# RF_INPUT_DIFF.net
KiCad netlist of a schematic drawn in EAGLE
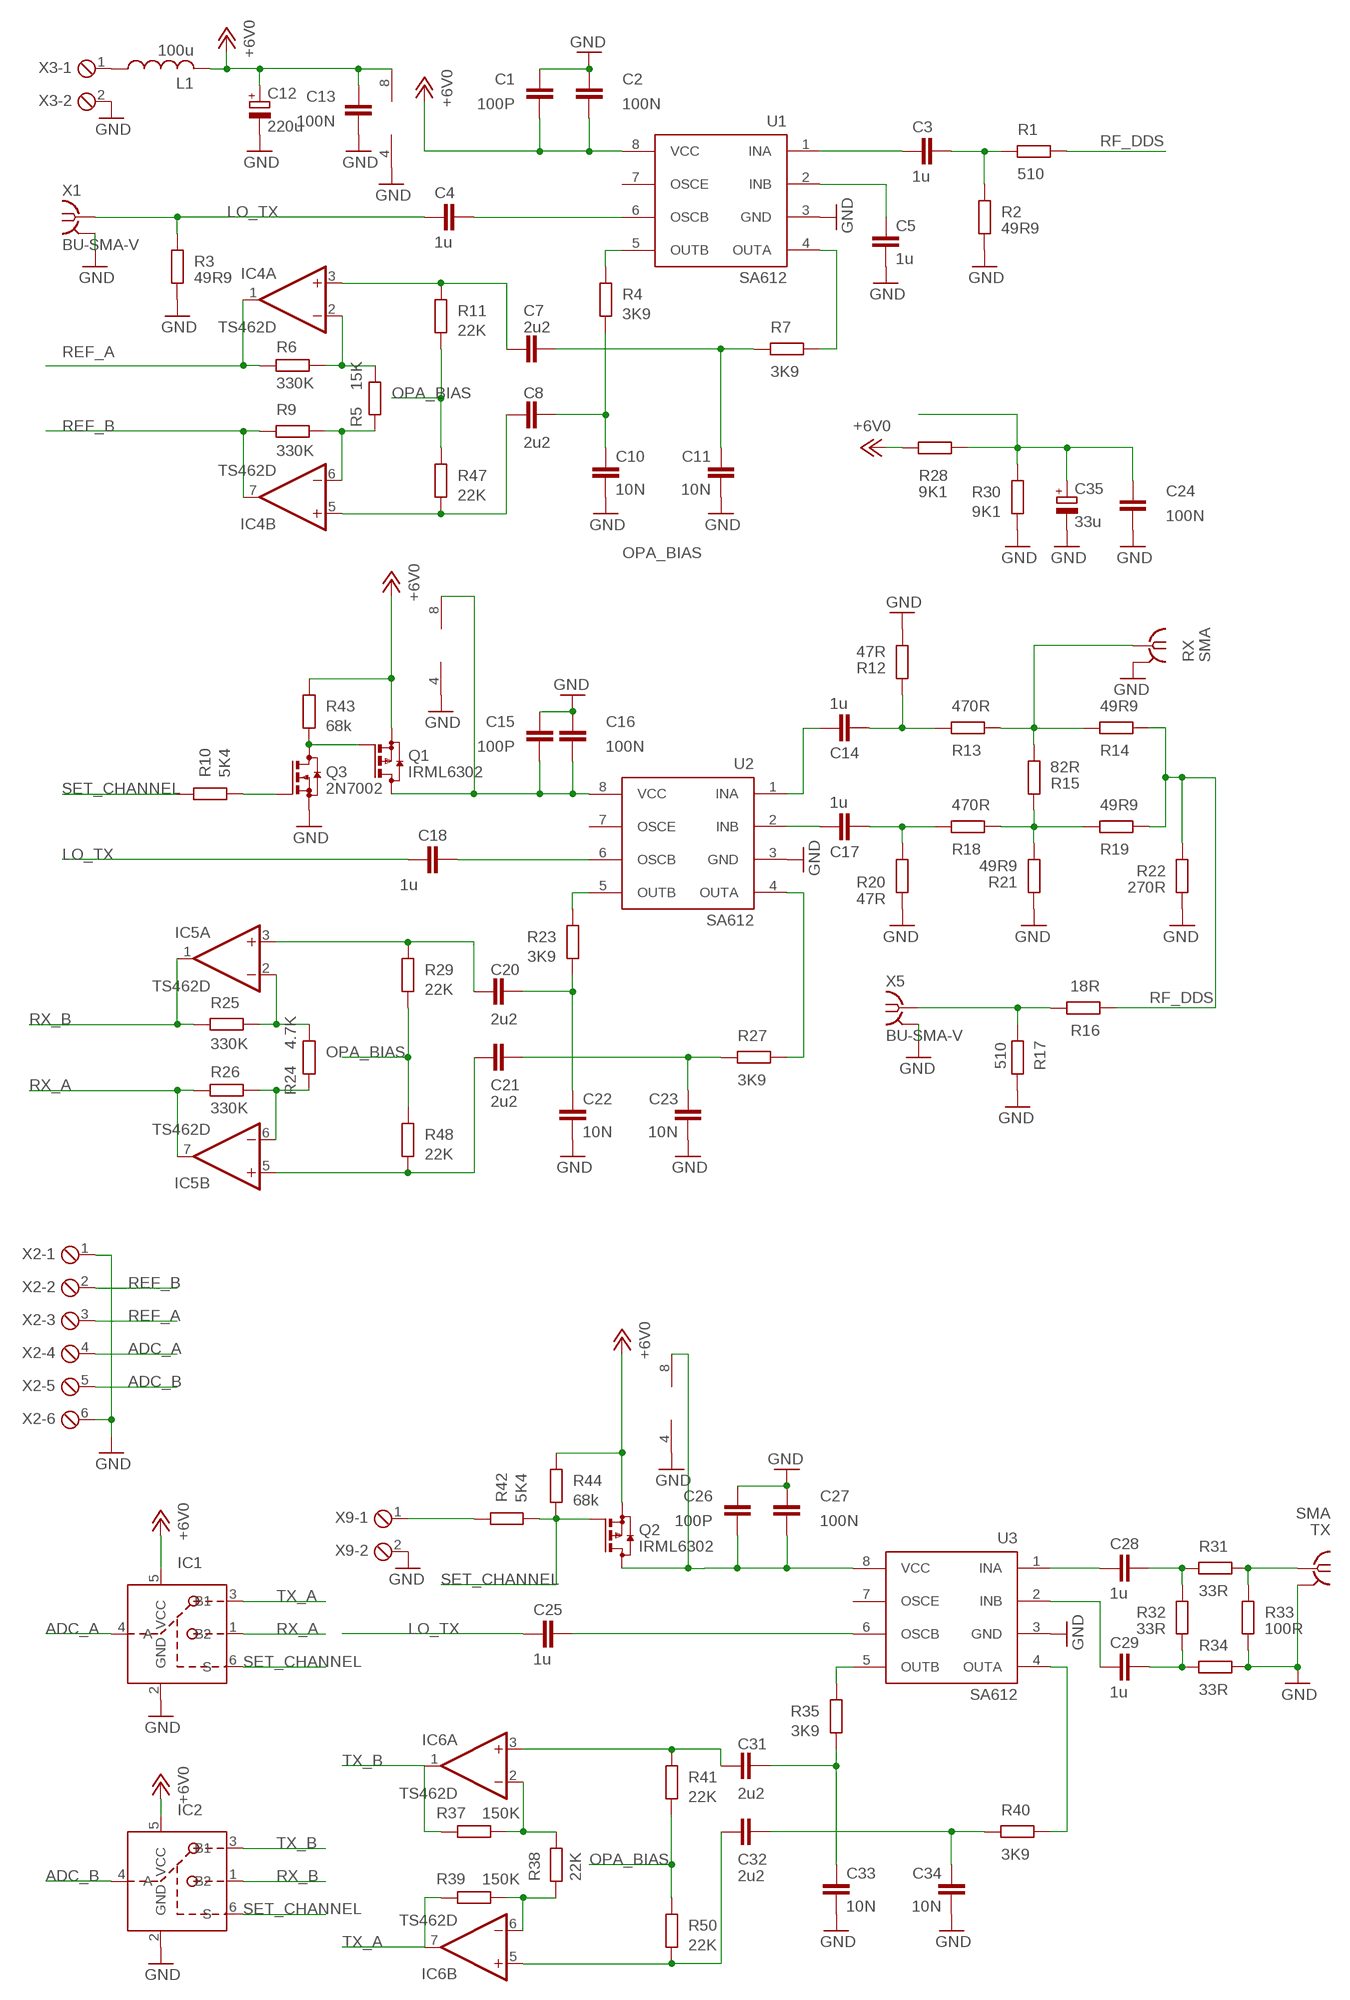
[diagram p0: schematic, sheet 1]

(export (version "E")
  (design (tool "Eeschema 10.0.6"))
  (components
    (comp (ref "C1")
      (value "100P")
      (footprint "eagle-import:C0805")
      (libsource (lib "eagle-import") (part "C-EUC0805"))
    )
    (comp (ref "C2")
      (value "100N")
      (footprint "eagle-import:C0603")
      (libsource (lib "eagle-import") (part "C-EUC0603"))
    )
    (comp (ref "C3")
      (value "1u")
      (footprint "eagle-import:C0603")
      (libsource (lib "eagle-import") (part "C-EUC0603"))
    )
    (comp (ref "C4")
      (value "1u")
      (footprint "eagle-import:C0805")
      (libsource (lib "eagle-import") (part "C-EUC0805"))
    )
    (comp (ref "C5")
      (value "1u")
      (footprint "eagle-import:C0603")
      (libsource (lib "eagle-import") (part "C-EUC0603"))
    )
    (comp (ref "C7")
      (value "2u2")
      (footprint "eagle-import:C0805")
      (libsource (lib "eagle-import") (part "C-EUC0805"))
    )
    (comp (ref "C8")
      (value "2u2")
      (footprint "eagle-import:C0805")
      (libsource (lib "eagle-import") (part "C-EUC0805"))
    )
    (comp (ref "C10")
      (value "10N")
      (footprint "eagle-import:C0805")
      (libsource (lib "eagle-import") (part "C-EUC0805"))
    )
    (comp (ref "C11")
      (value "10N")
      (footprint "eagle-import:C0805")
      (libsource (lib "eagle-import") (part "C-EUC0805"))
    )
    (comp (ref "C12")
      (value "220u")
      (footprint "eagle-import:153CLV-0605")
      (libsource (lib "eagle-import") (part "CPOL-EU153CLV-0605"))
    )
    (comp (ref "C13")
      (value "100N")
      (footprint "eagle-import:C0603")
      (libsource (lib "eagle-import") (part "C-EUC0603"))
    )
    (comp (ref "C14")
      (value "1u")
      (footprint "eagle-import:C0603")
      (libsource (lib "eagle-import") (part "C-EUC0603"))
    )
    (comp (ref "C15")
      (value "100P")
      (footprint "eagle-import:C0805")
      (libsource (lib "eagle-import") (part "C-EUC0805"))
    )
    (comp (ref "C16")
      (value "100N")
      (footprint "eagle-import:C0603")
      (libsource (lib "eagle-import") (part "C-EUC0603"))
    )
    (comp (ref "C17")
      (value "1u")
      (footprint "eagle-import:C0603")
      (libsource (lib "eagle-import") (part "C-EUC0603"))
    )
    (comp (ref "C18")
      (value "1u")
      (footprint "eagle-import:C0805")
      (libsource (lib "eagle-import") (part "C-EUC0805"))
    )
    (comp (ref "C20")
      (value "2u2")
      (footprint "eagle-import:C0805")
      (libsource (lib "eagle-import") (part "C-EUC0805"))
    )
    (comp (ref "C21")
      (value "2u2")
      (footprint "eagle-import:C0805")
      (libsource (lib "eagle-import") (part "C-EUC0805"))
    )
    (comp (ref "C22")
      (value "10N")
      (footprint "eagle-import:C0805")
      (libsource (lib "eagle-import") (part "C-EUC0805"))
    )
    (comp (ref "C23")
      (value "10N")
      (footprint "eagle-import:C0805")
      (libsource (lib "eagle-import") (part "C-EUC0805"))
    )
    (comp (ref "C24")
      (value "100N")
      (footprint "eagle-import:C0603")
      (libsource (lib "eagle-import") (part "C-EUC0603"))
    )
    (comp (ref "C25")
      (value "1u")
      (footprint "eagle-import:C0805")
      (libsource (lib "eagle-import") (part "C-EUC0805"))
    )
    (comp (ref "C26")
      (value "100P")
      (footprint "eagle-import:C0805")
      (libsource (lib "eagle-import") (part "C-EUC0805"))
    )
    (comp (ref "C27")
      (value "100N")
      (footprint "eagle-import:C0603")
      (libsource (lib "eagle-import") (part "C-EUC0603"))
    )
    (comp (ref "C28")
      (value "1u")
      (footprint "eagle-import:C0603")
      (libsource (lib "eagle-import") (part "C-EUC0603"))
    )
    (comp (ref "C29")
      (value "1u")
      (footprint "eagle-import:C0603")
      (libsource (lib "eagle-import") (part "C-EUC0603"))
    )
    (comp (ref "C31")
      (value "2u2")
      (footprint "eagle-import:C0805")
      (libsource (lib "eagle-import") (part "C-EUC0805"))
    )
    (comp (ref "C32")
      (value "2u2")
      (footprint "eagle-import:C0805")
      (libsource (lib "eagle-import") (part "C-EUC0805"))
    )
    (comp (ref "C33")
      (value "10N")
      (footprint "eagle-import:C0805")
      (libsource (lib "eagle-import") (part "C-EUC0805"))
    )
    (comp (ref "C34")
      (value "10N")
      (footprint "eagle-import:C0805")
      (libsource (lib "eagle-import") (part "C-EUC0805"))
    )
    (comp (ref "C35")
      (value "33u")
      (footprint "eagle-import:153CLV-0605")
      (libsource (lib "eagle-import") (part "CPOL-EU153CLV-0605"))
    )
    (comp (ref "IC1")
      (value "SN74LVC1G3157DBVR")
      (footprint "eagle-import:SOT23-6")
      (libsource (lib "eagle-import") (part "SN74LVC1G3157DBVR"))
    )
    (comp (ref "IC2")
      (value "SN74LVC1G3157DBVR")
      (footprint "eagle-import:SOT23-6")
      (libsource (lib "eagle-import") (part "SN74LVC1G3157DBVR"))
    )
    (comp (ref "IC4")
      (value "TS462D")
      (footprint "eagle-import:SO08")
      (libsource (lib "eagle-import") (part "LM358D"))
    )
    (comp (ref "IC5")
      (value "TS462D")
      (footprint "eagle-import:SO08")
      (libsource (lib "eagle-import") (part "LM358D"))
    )
    (comp (ref "IC6")
      (value "TS462D")
      (footprint "eagle-import:SO08")
      (libsource (lib "eagle-import") (part "LM358D"))
    )
    (comp (ref "L1")
      (value "100u")
      (footprint "eagle-import:0207_12")
      (libsource (lib "eagle-import") (part "L-US0207/12"))
    )
    (comp (ref "Q1")
      (value "IRML6302")
      (footprint "eagle-import:SOT23")
      (libsource (lib "eagle-import") (part "BSS84"))
    )
    (comp (ref "Q2")
      (value "IRML6302")
      (footprint "eagle-import:SOT23")
      (libsource (lib "eagle-import") (part "BSS84"))
    )
    (comp (ref "Q3")
      (value "2N7002")
      (footprint "eagle-import:SOT23")
      (libsource (lib "eagle-import") (part "BSS123"))
    )
    (comp (ref "R1")
      (value "510")
      (footprint "eagle-import:R0603")
      (libsource (lib "eagle-import") (part "R-EU_R0603"))
    )
    (comp (ref "R2")
      (value "49R9")
      (footprint "eagle-import:R0805")
      (libsource (lib "eagle-import") (part "R-EU_R0805"))
    )
    (comp (ref "R3")
      (value "49R9")
      (footprint "eagle-import:R0805")
      (libsource (lib "eagle-import") (part "R-EU_R0805"))
    )
    (comp (ref "R4")
      (value "3K9")
      (footprint "eagle-import:R0603")
      (libsource (lib "eagle-import") (part "R-EU_R0603"))
    )
    (comp (ref "R5")
      (value "15K")
      (footprint "eagle-import:R0603")
      (libsource (lib "eagle-import") (part "R-EU_R0603"))
    )
    (comp (ref "R6")
      (value "330K")
      (footprint "eagle-import:R0603")
      (libsource (lib "eagle-import") (part "R-EU_R0603"))
    )
    (comp (ref "R7")
      (value "3K9")
      (footprint "eagle-import:R0603")
      (libsource (lib "eagle-import") (part "R-EU_R0603"))
    )
    (comp (ref "R9")
      (value "330K")
      (footprint "eagle-import:R0603")
      (libsource (lib "eagle-import") (part "R-EU_R0603"))
    )
    (comp (ref "R10")
      (value "5K4")
      (footprint "eagle-import:R0603")
      (libsource (lib "eagle-import") (part "R-EU_R0603"))
    )
    (comp (ref "R11")
      (value "22K")
      (footprint "eagle-import:R0603")
      (libsource (lib "eagle-import") (part "R-EU_R0603"))
    )
    (comp (ref "R12")
      (value "47R")
      (footprint "eagle-import:R0603")
      (libsource (lib "eagle-import") (part "R-EU_R0603"))
    )
    (comp (ref "R13")
      (value "470R")
      (footprint "eagle-import:R0603")
      (libsource (lib "eagle-import") (part "R-EU_R0603"))
    )
    (comp (ref "R14")
      (value "49R9")
      (footprint "eagle-import:R0805")
      (libsource (lib "eagle-import") (part "R-EU_R0805"))
    )
    (comp (ref "R15")
      (value "82R")
      (footprint "eagle-import:R0603")
      (libsource (lib "eagle-import") (part "R-EU_R0603"))
    )
    (comp (ref "R16")
      (value "18R")
      (footprint "eagle-import:R0603")
      (libsource (lib "eagle-import") (part "R-EU_R0603"))
    )
    (comp (ref "R17")
      (value "510")
      (footprint "eagle-import:R0603")
      (libsource (lib "eagle-import") (part "R-EU_R0603"))
    )
    (comp (ref "R18")
      (value "470R")
      (footprint "eagle-import:R0603")
      (libsource (lib "eagle-import") (part "R-EU_R0603"))
    )
    (comp (ref "R19")
      (value "49R9")
      (footprint "eagle-import:R0805")
      (libsource (lib "eagle-import") (part "R-EU_R0805"))
    )
    (comp (ref "R20")
      (value "47R")
      (footprint "eagle-import:R0603")
      (libsource (lib "eagle-import") (part "R-EU_R0603"))
    )
    (comp (ref "R21")
      (value "49R9")
      (footprint "eagle-import:R0805")
      (libsource (lib "eagle-import") (part "R-EU_R0805"))
    )
    (comp (ref "R22")
      (value "270R")
      (footprint "eagle-import:R0603")
      (libsource (lib "eagle-import") (part "R-EU_R0603"))
    )
    (comp (ref "R23")
      (value "3K9")
      (footprint "eagle-import:R0603")
      (libsource (lib "eagle-import") (part "R-EU_R0603"))
    )
    (comp (ref "R24")
      (value "4.7K")
      (footprint "eagle-import:R0603")
      (libsource (lib "eagle-import") (part "R-EU_R0603"))
    )
    (comp (ref "R25")
      (value "330K")
      (footprint "eagle-import:R0603")
      (libsource (lib "eagle-import") (part "R-EU_R0603"))
    )
    (comp (ref "R26")
      (value "330K")
      (footprint "eagle-import:R0603")
      (libsource (lib "eagle-import") (part "R-EU_R0603"))
    )
    (comp (ref "R27")
      (value "3K9")
      (footprint "eagle-import:R0603")
      (libsource (lib "eagle-import") (part "R-EU_R0603"))
    )
    (comp (ref "R28")
      (value "9K1")
      (footprint "eagle-import:R0603")
      (libsource (lib "eagle-import") (part "R-EU_R0603"))
    )
    (comp (ref "R29")
      (value "22K")
      (footprint "eagle-import:R0603")
      (libsource (lib "eagle-import") (part "R-EU_R0603"))
    )
    (comp (ref "R30")
      (value "9K1")
      (footprint "eagle-import:R0603")
      (libsource (lib "eagle-import") (part "R-EU_R0603"))
    )
    (comp (ref "R31")
      (value "33R")
      (footprint "eagle-import:R0603")
      (libsource (lib "eagle-import") (part "R-EU_R0603"))
    )
    (comp (ref "R32")
      (value "33R")
      (footprint "eagle-import:R0603")
      (libsource (lib "eagle-import") (part "R-EU_R0603"))
    )
    (comp (ref "R33")
      (value "100R")
      (footprint "eagle-import:R0603")
      (libsource (lib "eagle-import") (part "R-EU_R0603"))
    )
    (comp (ref "R34")
      (value "33R")
      (footprint "eagle-import:R0603")
      (libsource (lib "eagle-import") (part "R-EU_R0603"))
    )
    (comp (ref "R35")
      (value "3K9")
      (footprint "eagle-import:R0603")
      (libsource (lib "eagle-import") (part "R-EU_R0603"))
    )
    (comp (ref "R37")
      (value "150K")
      (footprint "eagle-import:R0603")
      (libsource (lib "eagle-import") (part "R-EU_R0603"))
    )
    (comp (ref "R38")
      (value "22K")
      (footprint "eagle-import:R0603")
      (libsource (lib "eagle-import") (part "R-EU_R0603"))
    )
    (comp (ref "R39")
      (value "150K")
      (footprint "eagle-import:R0603")
      (libsource (lib "eagle-import") (part "R-EU_R0603"))
    )
    (comp (ref "R40")
      (value "3K9")
      (footprint "eagle-import:R0603")
      (libsource (lib "eagle-import") (part "R-EU_R0603"))
    )
    (comp (ref "R41")
      (value "22K")
      (footprint "eagle-import:R0603")
      (libsource (lib "eagle-import") (part "R-EU_R0603"))
    )
    (comp (ref "R42")
      (value "5K4")
      (footprint "eagle-import:R0603")
      (libsource (lib "eagle-import") (part "R-EU_R0603"))
    )
    (comp (ref "R43")
      (value "68k")
      (footprint "eagle-import:R0603")
      (libsource (lib "eagle-import") (part "R-EU_R0603"))
    )
    (comp (ref "R44")
      (value "68k")
      (footprint "eagle-import:R0603")
      (libsource (lib "eagle-import") (part "R-EU_R0603"))
    )
    (comp (ref "R47")
      (value "22K")
      (footprint "eagle-import:R0603")
      (libsource (lib "eagle-import") (part "R-EU_R0603"))
    )
    (comp (ref "R48")
      (value "22K")
      (footprint "eagle-import:R0603")
      (libsource (lib "eagle-import") (part "R-EU_R0603"))
    )
    (comp (ref "R50")
      (value "22K")
      (footprint "eagle-import:R0603")
      (libsource (lib "eagle-import") (part "R-EU_R0603"))
    )
    (comp (ref "RX")
      (value "SMA")
      (footprint "eagle-import:J502-ND-142-0701-801_806")
      (fields (field (name "MF") "JOHNSON COMPONENTS") (field (name "MPN") "142-0701-801"))
      (libsource (lib "eagle-import") (part "SMA-142-0701-801/806"))
    )
    (comp (ref "TX")
      (value "SMA")
      (footprint "eagle-import:J502-ND-142-0701-801_806")
      (fields (field (name "MF") "JOHNSON COMPONENTS") (field (name "MPN") "142-0701-801"))
      (libsource (lib "eagle-import") (part "SMA-142-0701-801/806"))
    )
    (comp (ref "U1")
      (value "SA612")
      (footprint "eagle-import:SO8")
      (libsource (lib "eagle-import") (part "SA612"))
    )
    (comp (ref "U2")
      (value "SA612")
      (footprint "eagle-import:SO8")
      (libsource (lib "eagle-import") (part "SA612"))
    )
    (comp (ref "U3")
      (value "SA612")
      (footprint "eagle-import:SO8")
      (libsource (lib "eagle-import") (part "SA612"))
    )
    (comp (ref "X1")
      (value "BU-SMA-V")
      (footprint "eagle-import:BU-SMA-V")
      (libsource (lib "eagle-import") (part "BU-SMA-V"))
    )
    (comp (ref "X2")
      (value "MPT6")
      (footprint "eagle-import:6POL254")
      (libsource (lib "eagle-import") (part "MPT6"))
    )
    (comp (ref "X3")
      (value "MPT2")
      (footprint "eagle-import:2POL254")
      (libsource (lib "eagle-import") (part "MPT2"))
    )
    (comp (ref "X5")
      (value "BU-SMA-V")
      (footprint "eagle-import:BU-SMA-V")
      (libsource (lib "eagle-import") (part "BU-SMA-V"))
    )
    (comp (ref "X9")
      (value "MPT2")
      (footprint "eagle-import:2POL254")
      (libsource (lib "eagle-import") (part "MPT2"))
    )
  )
  (nets
    (net (code "1") (name "+6V0") (class "Default")
      (node (ref "C1") (pin "1") (pinfunction "1_1") (pintype "passive"))
      (node (ref "C12") (pin "+") (pinfunction "+_+") (pintype "passive"))
      (node (ref "C13") (pin "1") (pinfunction "1_1") (pintype "passive"))
      (node (ref "C2") (pin "1") (pinfunction "1_1") (pintype "passive"))
      (node (ref "IC1") (pin "5") (pinfunction "VCC_5") (pintype "power_in"))
      (node (ref "IC2") (pin "5") (pinfunction "VCC_5") (pintype "power_in"))
      (node (ref "IC4") (pin "8") (pinfunction "V+_8") (pintype "power_in"))
      (node (ref "L1") (pin "2") (pinfunction "2_2") (pintype "passive"))
      (node (ref "Q1") (pin "2") (pinfunction "S_2") (pintype "passive"))
      (node (ref "Q2") (pin "2") (pinfunction "S_2") (pintype "passive"))
      (node (ref "R28") (pin "2") (pinfunction "2_2") (pintype "passive"))
      (node (ref "R43") (pin "1") (pinfunction "1_1") (pintype "passive"))
      (node (ref "R44") (pin "1") (pinfunction "1_1") (pintype "passive"))
      (node (ref "U1") (pin "8") (pinfunction "VCC_8") (pintype "bidirectional"))
    )
    (net (code "2") (name "/ADC_A") (class "Default")
      (node (ref "IC1") (pin "4") (pinfunction "A_4") (pintype "bidirectional"))
      (node (ref "X2") (pin "4") (pinfunction "1_4") (pintype "passive"))
    )
    (net (code "3") (name "/ADC_B") (class "Default")
      (node (ref "IC2") (pin "4") (pinfunction "A_4") (pintype "bidirectional"))
      (node (ref "X2") (pin "5") (pinfunction "1_5") (pintype "passive"))
    )
    (net (code "4") (name "/LO_TX") (class "Default")
      (node (ref "C18") (pin "1") (pinfunction "1_1") (pintype "passive"))
      (node (ref "C25") (pin "1") (pinfunction "1_1") (pintype "passive"))
      (node (ref "C4") (pin "1") (pinfunction "1_1") (pintype "passive"))
      (node (ref "R3") (pin "1") (pinfunction "1_1") (pintype "passive"))
      (node (ref "X1") (pin "1") (pinfunction "1_1") (pintype "passive"))
    )
    (net (code "5") (name "/OPA_BIAS") (class "Default")
      (node (ref "C24") (pin "2") (pinfunction "2_2") (pintype "passive"))
      (node (ref "C35") (pin "+") (pinfunction "+_+") (pintype "passive"))
      (node (ref "R11") (pin "2") (pinfunction "2_2") (pintype "passive"))
      (node (ref "R28") (pin "1") (pinfunction "1_1") (pintype "passive"))
      (node (ref "R29") (pin "2") (pinfunction "2_2") (pintype "passive"))
      (node (ref "R30") (pin "1") (pinfunction "1_1") (pintype "passive"))
      (node (ref "R41") (pin "2") (pinfunction "2_2") (pintype "passive"))
      (node (ref "R47") (pin "1") (pinfunction "1_1") (pintype "passive"))
      (node (ref "R48") (pin "1") (pinfunction "1_1") (pintype "passive"))
      (node (ref "R50") (pin "1") (pinfunction "1_1") (pintype "passive"))
    )
    (net (code "6") (name "/REF_A") (class "Default")
      (node (ref "IC4") (pin "1") (pinfunction "OUT_1") (pintype "output"))
      (node (ref "R6") (pin "2") (pinfunction "2_2") (pintype "passive"))
      (node (ref "X2") (pin "3") (pinfunction "1_3") (pintype "passive"))
    )
    (net (code "7") (name "/REF_B") (class "Default")
      (node (ref "IC4") (pin "7") (pinfunction "OUT_7") (pintype "output"))
      (node (ref "R9") (pin "2") (pinfunction "2_2") (pintype "passive"))
      (node (ref "X2") (pin "2") (pinfunction "1_2") (pintype "passive"))
    )
    (net (code "8") (name "/RF_DDS") (class "Default")
      (node (ref "R1") (pin "1") (pinfunction "1_1") (pintype "passive"))
      (node (ref "R16") (pin "1") (pinfunction "1_1") (pintype "passive"))
      (node (ref "R17") (pin "1") (pinfunction "1_1") (pintype "passive"))
      (node (ref "X5") (pin "1") (pinfunction "1_1") (pintype "passive"))
    )
    (net (code "9") (name "/RX_A") (class "Default")
      (node (ref "IC1") (pin "1") (pinfunction "B2_1") (pintype "bidirectional"))
      (node (ref "IC5") (pin "7") (pinfunction "OUT_7") (pintype "output"))
      (node (ref "R26") (pin "2") (pinfunction "2_2") (pintype "passive"))
    )
    (net (code "10") (name "/RX_B") (class "Default")
      (node (ref "IC2") (pin "1") (pinfunction "B2_1") (pintype "bidirectional"))
      (node (ref "IC5") (pin "1") (pinfunction "OUT_1") (pintype "output"))
      (node (ref "R25") (pin "2") (pinfunction "2_2") (pintype "passive"))
    )
    (net (code "11") (name "/SET_CHANNEL") (class "Default")
      (node (ref "IC1") (pin "6") (pinfunction "S_6") (pintype "bidirectional"))
      (node (ref "IC2") (pin "6") (pinfunction "S_6") (pintype "bidirectional"))
      (node (ref "Q2") (pin "1") (pinfunction "G_1") (pintype "passive"))
      (node (ref "R10") (pin "1") (pinfunction "1_1") (pintype "passive"))
      (node (ref "R42") (pin "2") (pinfunction "2_2") (pintype "passive"))
      (node (ref "R44") (pin "2") (pinfunction "2_2") (pintype "passive"))
    )
    (net (code "12") (name "/TX_A") (class "Default")
      (node (ref "IC1") (pin "3") (pinfunction "B1_3") (pintype "bidirectional"))
      (node (ref "IC6") (pin "7") (pinfunction "OUT_7") (pintype "output"))
      (node (ref "R39") (pin "2") (pinfunction "2_2") (pintype "passive"))
    )
    (net (code "13") (name "/TX_B") (class "Default")
      (node (ref "IC2") (pin "3") (pinfunction "B1_3") (pintype "bidirectional"))
      (node (ref "IC6") (pin "1") (pinfunction "OUT_1") (pintype "output"))
      (node (ref "R37") (pin "2") (pinfunction "2_2") (pintype "passive"))
    )
    (net (code "14") (name "GND") (class "Default")
      (node (ref "C1") (pin "2") (pinfunction "2_2") (pintype "passive"))
      (node (ref "C10") (pin "2") (pinfunction "2_2") (pintype "passive"))
      (node (ref "C11") (pin "2") (pinfunction "2_2") (pintype "passive"))
      (node (ref "C12") (pin "-") (pinfunction "-_-") (pintype "passive"))
      (node (ref "C13") (pin "2") (pinfunction "2_2") (pintype "passive"))
      (node (ref "C15") (pin "2") (pinfunction "2_2") (pintype "passive"))
      (node (ref "C16") (pin "2") (pinfunction "2_2") (pintype "passive"))
      (node (ref "C2") (pin "2") (pinfunction "2_2") (pintype "passive"))
      (node (ref "C22") (pin "2") (pinfunction "2_2") (pintype "passive"))
      (node (ref "C23") (pin "2") (pinfunction "2_2") (pintype "passive"))
      (node (ref "C24") (pin "1") (pinfunction "1_1") (pintype "passive"))
      (node (ref "C26") (pin "2") (pinfunction "2_2") (pintype "passive"))
      (node (ref "C27") (pin "2") (pinfunction "2_2") (pintype "passive"))
      (node (ref "C33") (pin "2") (pinfunction "2_2") (pintype "passive"))
      (node (ref "C34") (pin "2") (pinfunction "2_2") (pintype "passive"))
      (node (ref "C35") (pin "-") (pinfunction "-_-") (pintype "passive"))
      (node (ref "C5") (pin "2") (pinfunction "2_2") (pintype "passive"))
      (node (ref "IC1") (pin "2") (pinfunction "GND_2") (pintype "power_in"))
      (node (ref "IC2") (pin "2") (pinfunction "GND_2") (pintype "power_in"))
      (node (ref "IC4") (pin "4") (pinfunction "V-_4") (pintype "power_in"))
      (node (ref "IC5") (pin "4") (pinfunction "V-_4") (pintype "power_in"))
      (node (ref "IC6") (pin "4") (pinfunction "V-_4") (pintype "power_in"))
      (node (ref "Q3") (pin "2") (pinfunction "S_2") (pintype "passive"))
      (node (ref "R12") (pin "2") (pinfunction "2_2") (pintype "passive"))
      (node (ref "R17") (pin "2") (pinfunction "2_2") (pintype "passive"))
      (node (ref "R2") (pin "1") (pinfunction "1_1") (pintype "passive"))
      (node (ref "R20") (pin "1") (pinfunction "1_1") (pintype "passive"))
      (node (ref "R21") (pin "1") (pinfunction "1_1") (pintype "passive"))
      (node (ref "R22") (pin "2") (pinfunction "2_2") (pintype "passive"))
      (node (ref "R3") (pin "2") (pinfunction "2_2") (pintype "passive"))
      (node (ref "R30") (pin "2") (pinfunction "2_2") (pintype "passive"))
      (node (ref "R33") (pin "2") (pinfunction "2_2") (pintype "passive"))
      (node (ref "R34") (pin "1") (pinfunction "1_1") (pintype "passive"))
      (node (ref "RX") (pin "G@1") (pinfunction "2_G@1") (pintype "passive"))
      (node (ref "RX") (pin "G@2") (pinfunction "2_G@2") (pintype "passive"))
      (node (ref "RX") (pin "G@3") (pinfunction "2_G@3") (pintype "passive"))
      (node (ref "RX") (pin "G@4") (pinfunction "2_G@4") (pintype "passive"))
      (node (ref "TX") (pin "G@1") (pinfunction "2_G@1") (pintype "passive"))
      (node (ref "TX") (pin "G@2") (pinfunction "2_G@2") (pintype "passive"))
      (node (ref "TX") (pin "G@3") (pinfunction "2_G@3") (pintype "passive"))
      (node (ref "TX") (pin "G@4") (pinfunction "2_G@4") (pintype "passive"))
      (node (ref "U1") (pin "3") (pinfunction "GND_3") (pintype "bidirectional"))
      (node (ref "U2") (pin "3") (pinfunction "GND_3") (pintype "bidirectional"))
      (node (ref "U3") (pin "3") (pinfunction "GND_3") (pintype "bidirectional"))
      (node (ref "X1") (pin "2") (pinfunction "2_2") (pintype "passive"))
      (node (ref "X1") (pin "3") (pinfunction "2_3") (pintype "passive"))
      (node (ref "X1") (pin "4") (pinfunction "2_4") (pintype "passive"))
      (node (ref "X1") (pin "5") (pinfunction "2_5") (pintype "passive"))
      (node (ref "X2") (pin "1") (pinfunction "1_1") (pintype "passive"))
      (node (ref "X2") (pin "6") (pinfunction "1_6") (pintype "passive"))
      (node (ref "X3") (pin "2") (pinfunction "1_2") (pintype "passive"))
      (node (ref "X5") (pin "2") (pinfunction "2_2") (pintype "passive"))
      (node (ref "X5") (pin "3") (pinfunction "2_3") (pintype "passive"))
      (node (ref "X5") (pin "4") (pinfunction "2_4") (pintype "passive"))
      (node (ref "X5") (pin "5") (pinfunction "2_5") (pintype "passive"))
      (node (ref "X9") (pin "2") (pinfunction "1_2") (pintype "passive"))
    )
    (net (code "15") (name "Net-(C3-Pad2)") (class "Default")
      (node (ref "C3") (pin "2") (pinfunction "2_2") (pintype "passive"))
      (node (ref "R1") (pin "2") (pinfunction "2_2") (pintype "passive"))
      (node (ref "R2") (pin "2") (pinfunction "2_2") (pintype "passive"))
    )
    (net (code "16") (name "Net-(C10-Pad1)") (class "Default")
      (node (ref "C10") (pin "1") (pinfunction "1_1") (pintype "passive"))
      (node (ref "C8") (pin "2") (pinfunction "2_2") (pintype "passive"))
      (node (ref "R4") (pin "2") (pinfunction "2_2") (pintype "passive"))
    )
    (net (code "17") (name "Net-(C11-Pad1)") (class "Default")
      (node (ref "C11") (pin "1") (pinfunction "1_1") (pintype "passive"))
      (node (ref "C7") (pin "2") (pinfunction "2_2") (pintype "passive"))
      (node (ref "R7") (pin "2") (pinfunction "2_2") (pintype "passive"))
    )
    (net (code "18") (name "Net-(C14-Pad2)") (class "Default")
      (node (ref "C14") (pin "2") (pinfunction "2_2") (pintype "passive"))
      (node (ref "R12") (pin "1") (pinfunction "1_1") (pintype "passive"))
      (node (ref "R13") (pin "2") (pinfunction "2_2") (pintype "passive"))
    )
    (net (code "19") (name "Net-(C17-Pad2)") (class "Default")
      (node (ref "C17") (pin "2") (pinfunction "2_2") (pintype "passive"))
      (node (ref "R18") (pin "2") (pinfunction "2_2") (pintype "passive"))
      (node (ref "R20") (pin "2") (pinfunction "2_2") (pintype "passive"))
    )
    (net (code "20") (name "Net-(C20-Pad2)") (class "Default")
      (node (ref "C20") (pin "2") (pinfunction "2_2") (pintype "passive"))
      (node (ref "C22") (pin "1") (pinfunction "1_1") (pintype "passive"))
      (node (ref "R23") (pin "2") (pinfunction "2_2") (pintype "passive"))
    )
    (net (code "21") (name "Net-(C21-Pad2)") (class "Default")
      (node (ref "C21") (pin "2") (pinfunction "2_2") (pintype "passive"))
      (node (ref "C23") (pin "1") (pinfunction "1_1") (pintype "passive"))
      (node (ref "R27") (pin "2") (pinfunction "2_2") (pintype "passive"))
    )
    (net (code "22") (name "Net-(C28-Pad2)") (class "Default")
      (node (ref "C28") (pin "2") (pinfunction "2_2") (pintype "passive"))
      (node (ref "R31") (pin "2") (pinfunction "2_2") (pintype "passive"))
      (node (ref "R32") (pin "1") (pinfunction "1_1") (pintype "passive"))
    )
    (net (code "23") (name "Net-(C29-Pad2)") (class "Default")
      (node (ref "C29") (pin "2") (pinfunction "2_2") (pintype "passive"))
      (node (ref "R32") (pin "2") (pinfunction "2_2") (pintype "passive"))
      (node (ref "R34") (pin "2") (pinfunction "2_2") (pintype "passive"))
    )
    (net (code "24") (name "Net-(C31-Pad2)") (class "Default")
      (node (ref "C31") (pin "2") (pinfunction "2_2") (pintype "passive"))
      (node (ref "C33") (pin "1") (pinfunction "1_1") (pintype "passive"))
      (node (ref "R35") (pin "2") (pinfunction "2_2") (pintype "passive"))
    )
    (net (code "25") (name "Net-(C32-Pad2)") (class "Default")
      (node (ref "C32") (pin "2") (pinfunction "2_2") (pintype "passive"))
      (node (ref "C34") (pin "1") (pinfunction "1_1") (pintype "passive"))
      (node (ref "R40") (pin "2") (pinfunction "2_2") (pintype "passive"))
    )
    (net (code "26") (name "Net-(IC4A-+IN)") (class "Default")
      (node (ref "C7") (pin "1") (pinfunction "1_1") (pintype "passive"))
      (node (ref "IC4") (pin "3") (pinfunction "+IN_3") (pintype "input"))
      (node (ref "R11") (pin "1") (pinfunction "1_1") (pintype "passive"))
    )
    (net (code "27") (name "Net-(IC4A--IN)") (class "Default")
      (node (ref "IC4") (pin "2") (pinfunction "-IN_2") (pintype "input"))
      (node (ref "R5") (pin "1") (pinfunction "1_1") (pintype "passive"))
      (node (ref "R6") (pin "1") (pinfunction "1_1") (pintype "passive"))
    )
    (net (code "28") (name "Net-(IC4B-+IN)") (class "Default")
      (node (ref "C8") (pin "1") (pinfunction "1_1") (pintype "passive"))
      (node (ref "IC4") (pin "5") (pinfunction "+IN_5") (pintype "input"))
      (node (ref "R47") (pin "2") (pinfunction "2_2") (pintype "passive"))
    )
    (net (code "29") (name "Net-(IC4B--IN)") (class "Default")
      (node (ref "IC4") (pin "6") (pinfunction "-IN_6") (pintype "input"))
      (node (ref "R5") (pin "2") (pinfunction "2_2") (pintype "passive"))
      (node (ref "R9") (pin "1") (pinfunction "1_1") (pintype "passive"))
    )
    (net (code "30") (name "Net-(IC5A-+IN)") (class "Default")
      (node (ref "C20") (pin "1") (pinfunction "1_1") (pintype "passive"))
      (node (ref "IC5") (pin "3") (pinfunction "+IN_3") (pintype "input"))
      (node (ref "R29") (pin "1") (pinfunction "1_1") (pintype "passive"))
    )
    (net (code "31") (name "Net-(IC5A--IN)") (class "Default")
      (node (ref "IC5") (pin "2") (pinfunction "-IN_2") (pintype "input"))
      (node (ref "R24") (pin "1") (pinfunction "1_1") (pintype "passive"))
      (node (ref "R25") (pin "1") (pinfunction "1_1") (pintype "passive"))
    )
    (net (code "32") (name "Net-(IC5B-+IN)") (class "Default")
      (node (ref "C21") (pin "1") (pinfunction "1_1") (pintype "passive"))
      (node (ref "IC5") (pin "5") (pinfunction "+IN_5") (pintype "input"))
      (node (ref "R48") (pin "2") (pinfunction "2_2") (pintype "passive"))
    )
    (net (code "33") (name "Net-(IC5B--IN)") (class "Default")
      (node (ref "IC5") (pin "6") (pinfunction "-IN_6") (pintype "input"))
      (node (ref "R24") (pin "2") (pinfunction "2_2") (pintype "passive"))
      (node (ref "R26") (pin "1") (pinfunction "1_1") (pintype "passive"))
    )
    (net (code "34") (name "Net-(IC5C-V+)") (class "Default")
      (node (ref "C15") (pin "1") (pinfunction "1_1") (pintype "passive"))
      (node (ref "C16") (pin "1") (pinfunction "1_1") (pintype "passive"))
      (node (ref "IC5") (pin "8") (pinfunction "V+_8") (pintype "power_in"))
      (node (ref "Q1") (pin "3") (pinfunction "D_3") (pintype "passive"))
      (node (ref "U2") (pin "8") (pinfunction "VCC_8") (pintype "bidirectional"))
    )
    (net (code "35") (name "Net-(IC6A-+IN)") (class "Default")
      (node (ref "C31") (pin "1") (pinfunction "1_1") (pintype "passive"))
      (node (ref "IC6") (pin "3") (pinfunction "+IN_3") (pintype "input"))
      (node (ref "R41") (pin "1") (pinfunction "1_1") (pintype "passive"))
    )
    (net (code "36") (name "Net-(IC6A--IN)") (class "Default")
      (node (ref "IC6") (pin "2") (pinfunction "-IN_2") (pintype "input"))
      (node (ref "R37") (pin "1") (pinfunction "1_1") (pintype "passive"))
      (node (ref "R38") (pin "1") (pinfunction "1_1") (pintype "passive"))
    )
    (net (code "37") (name "Net-(IC6B-+IN)") (class "Default")
      (node (ref "C32") (pin "1") (pinfunction "1_1") (pintype "passive"))
      (node (ref "IC6") (pin "5") (pinfunction "+IN_5") (pintype "input"))
      (node (ref "R50") (pin "2") (pinfunction "2_2") (pintype "passive"))
    )
    (net (code "38") (name "Net-(IC6B--IN)") (class "Default")
      (node (ref "IC6") (pin "6") (pinfunction "-IN_6") (pintype "input"))
      (node (ref "R38") (pin "2") (pinfunction "2_2") (pintype "passive"))
      (node (ref "R39") (pin "1") (pinfunction "1_1") (pintype "passive"))
    )
    (net (code "39") (name "Net-(IC6C-V+)") (class "Default")
      (node (ref "C26") (pin "1") (pinfunction "1_1") (pintype "passive"))
      (node (ref "C27") (pin "1") (pinfunction "1_1") (pintype "passive"))
      (node (ref "IC6") (pin "8") (pinfunction "V+_8") (pintype "power_in"))
      (node (ref "Q2") (pin "3") (pinfunction "D_3") (pintype "passive"))
      (node (ref "U3") (pin "8") (pinfunction "VCC_8") (pintype "bidirectional"))
    )
    (net (code "40") (name "Net-(L1-Pad1)") (class "Default")
      (node (ref "L1") (pin "1") (pinfunction "1_1") (pintype "passive"))
      (node (ref "X3") (pin "1") (pinfunction "1_1") (pintype "passive"))
    )
    (net (code "41") (name "Net-(Q1-G)") (class "Default")
      (node (ref "Q1") (pin "1") (pinfunction "G_1") (pintype "passive"))
      (node (ref "Q3") (pin "3") (pinfunction "D_3") (pintype "passive"))
      (node (ref "R43") (pin "2") (pinfunction "2_2") (pintype "passive"))
    )
    (net (code "42") (name "Net-(Q3-G)") (class "Default")
      (node (ref "Q3") (pin "1") (pinfunction "G_1") (pintype "passive"))
      (node (ref "R10") (pin "2") (pinfunction "2_2") (pintype "passive"))
    )
    (net (code "43") (name "Net-(R13-Pad1)") (class "Default")
      (node (ref "R13") (pin "1") (pinfunction "1_1") (pintype "passive"))
      (node (ref "R14") (pin "2") (pinfunction "2_2") (pintype "passive"))
      (node (ref "R15") (pin "2") (pinfunction "2_2") (pintype "passive"))
      (node (ref "RX") (pin "1") (pinfunction "1_1") (pintype "passive"))
    )
    (net (code "44") (name "Net-(R14-Pad1)") (class "Default")
      (node (ref "R14") (pin "1") (pinfunction "1_1") (pintype "passive"))
      (node (ref "R16") (pin "2") (pinfunction "2_2") (pintype "passive"))
      (node (ref "R19") (pin "1") (pinfunction "1_1") (pintype "passive"))
      (node (ref "R22") (pin "1") (pinfunction "1_1") (pintype "passive"))
    )
    (net (code "45") (name "Net-(R15-Pad1)") (class "Default")
      (node (ref "R15") (pin "1") (pinfunction "1_1") (pintype "passive"))
      (node (ref "R18") (pin "1") (pinfunction "1_1") (pintype "passive"))
      (node (ref "R19") (pin "2") (pinfunction "2_2") (pintype "passive"))
      (node (ref "R21") (pin "2") (pinfunction "2_2") (pintype "passive"))
    )
    (net (code "46") (name "Net-(R31-Pad1)") (class "Default")
      (node (ref "R31") (pin "1") (pinfunction "1_1") (pintype "passive"))
      (node (ref "R33") (pin "1") (pinfunction "1_1") (pintype "passive"))
      (node (ref "TX") (pin "1") (pinfunction "1_1") (pintype "passive"))
    )
    (net (code "47") (name "Net-(R42-Pad1)") (class "Default")
      (node (ref "R42") (pin "1") (pinfunction "1_1") (pintype "passive"))
      (node (ref "X9") (pin "1") (pinfunction "1_1") (pintype "passive"))
    )
    (net (code "48") (name "Net-(U1-INA)") (class "Default")
      (node (ref "C3") (pin "1") (pinfunction "1_1") (pintype "passive"))
      (node (ref "U1") (pin "1") (pinfunction "INA_1") (pintype "bidirectional"))
    )
    (net (code "49") (name "Net-(U1-INB)") (class "Default")
      (node (ref "C5") (pin "1") (pinfunction "1_1") (pintype "passive"))
      (node (ref "U1") (pin "2") (pinfunction "INB_2") (pintype "bidirectional"))
    )
    (net (code "50") (name "Net-(U1-OSCB)") (class "Default")
      (node (ref "C4") (pin "2") (pinfunction "2_2") (pintype "passive"))
      (node (ref "U1") (pin "6") (pinfunction "OSCB_6") (pintype "bidirectional"))
    )
    (net (code "51") (name "Net-(U1-OUTA)") (class "Default")
      (node (ref "R7") (pin "1") (pinfunction "1_1") (pintype "passive"))
      (node (ref "U1") (pin "4") (pinfunction "OUTA_4") (pintype "bidirectional"))
    )
    (net (code "52") (name "Net-(U1-OUTB)") (class "Default")
      (node (ref "R4") (pin "1") (pinfunction "1_1") (pintype "passive"))
      (node (ref "U1") (pin "5") (pinfunction "OUTB_5") (pintype "bidirectional"))
    )
    (net (code "53") (name "Net-(U2-INA)") (class "Default")
      (node (ref "C14") (pin "1") (pinfunction "1_1") (pintype "passive"))
      (node (ref "U2") (pin "1") (pinfunction "INA_1") (pintype "bidirectional"))
    )
    (net (code "54") (name "Net-(U2-INB)") (class "Default")
      (node (ref "C17") (pin "1") (pinfunction "1_1") (pintype "passive"))
      (node (ref "U2") (pin "2") (pinfunction "INB_2") (pintype "bidirectional"))
    )
    (net (code "55") (name "Net-(U2-OSCB)") (class "Default")
      (node (ref "C18") (pin "2") (pinfunction "2_2") (pintype "passive"))
      (node (ref "U2") (pin "6") (pinfunction "OSCB_6") (pintype "bidirectional"))
    )
    (net (code "56") (name "Net-(U2-OUTA)") (class "Default")
      (node (ref "R27") (pin "1") (pinfunction "1_1") (pintype "passive"))
      (node (ref "U2") (pin "4") (pinfunction "OUTA_4") (pintype "bidirectional"))
    )
    (net (code "57") (name "Net-(U2-OUTB)") (class "Default")
      (node (ref "R23") (pin "1") (pinfunction "1_1") (pintype "passive"))
      (node (ref "U2") (pin "5") (pinfunction "OUTB_5") (pintype "bidirectional"))
    )
    (net (code "58") (name "Net-(U3-INA)") (class "Default")
      (node (ref "C28") (pin "1") (pinfunction "1_1") (pintype "passive"))
      (node (ref "U3") (pin "1") (pinfunction "INA_1") (pintype "bidirectional"))
    )
    (net (code "59") (name "Net-(U3-INB)") (class "Default")
      (node (ref "C29") (pin "1") (pinfunction "1_1") (pintype "passive"))
      (node (ref "U3") (pin "2") (pinfunction "INB_2") (pintype "bidirectional"))
    )
    (net (code "60") (name "Net-(U3-OSCB)") (class "Default")
      (node (ref "C25") (pin "2") (pinfunction "2_2") (pintype "passive"))
      (node (ref "U3") (pin "6") (pinfunction "OSCB_6") (pintype "bidirectional"))
    )
    (net (code "61") (name "Net-(U3-OUTA)") (class "Default")
      (node (ref "R40") (pin "1") (pinfunction "1_1") (pintype "passive"))
      (node (ref "U3") (pin "4") (pinfunction "OUTA_4") (pintype "bidirectional"))
    )
    (net (code "62") (name "Net-(U3-OUTB)") (class "Default")
      (node (ref "R35") (pin "1") (pinfunction "1_1") (pintype "passive"))
      (node (ref "U3") (pin "5") (pinfunction "OUTB_5") (pintype "bidirectional"))
    )
    (net (code "63") (name "unconnected-(U1-OSCE-Pad7)") (class "Default")
      (node (ref "U1") (pin "7") (pinfunction "OSCE_7") (pintype "bidirectional"))
    )
    (net (code "64") (name "unconnected-(U2-OSCE-Pad7)") (class "Default")
      (node (ref "U2") (pin "7") (pinfunction "OSCE_7") (pintype "bidirectional"))
    )
    (net (code "65") (name "unconnected-(U3-OSCE-Pad7)") (class "Default")
      (node (ref "U3") (pin "7") (pinfunction "OSCE_7") (pintype "bidirectional"))
    )
  )
)
